# MCU.net
KiCad netlist of a schematic drawn in Altium Designer
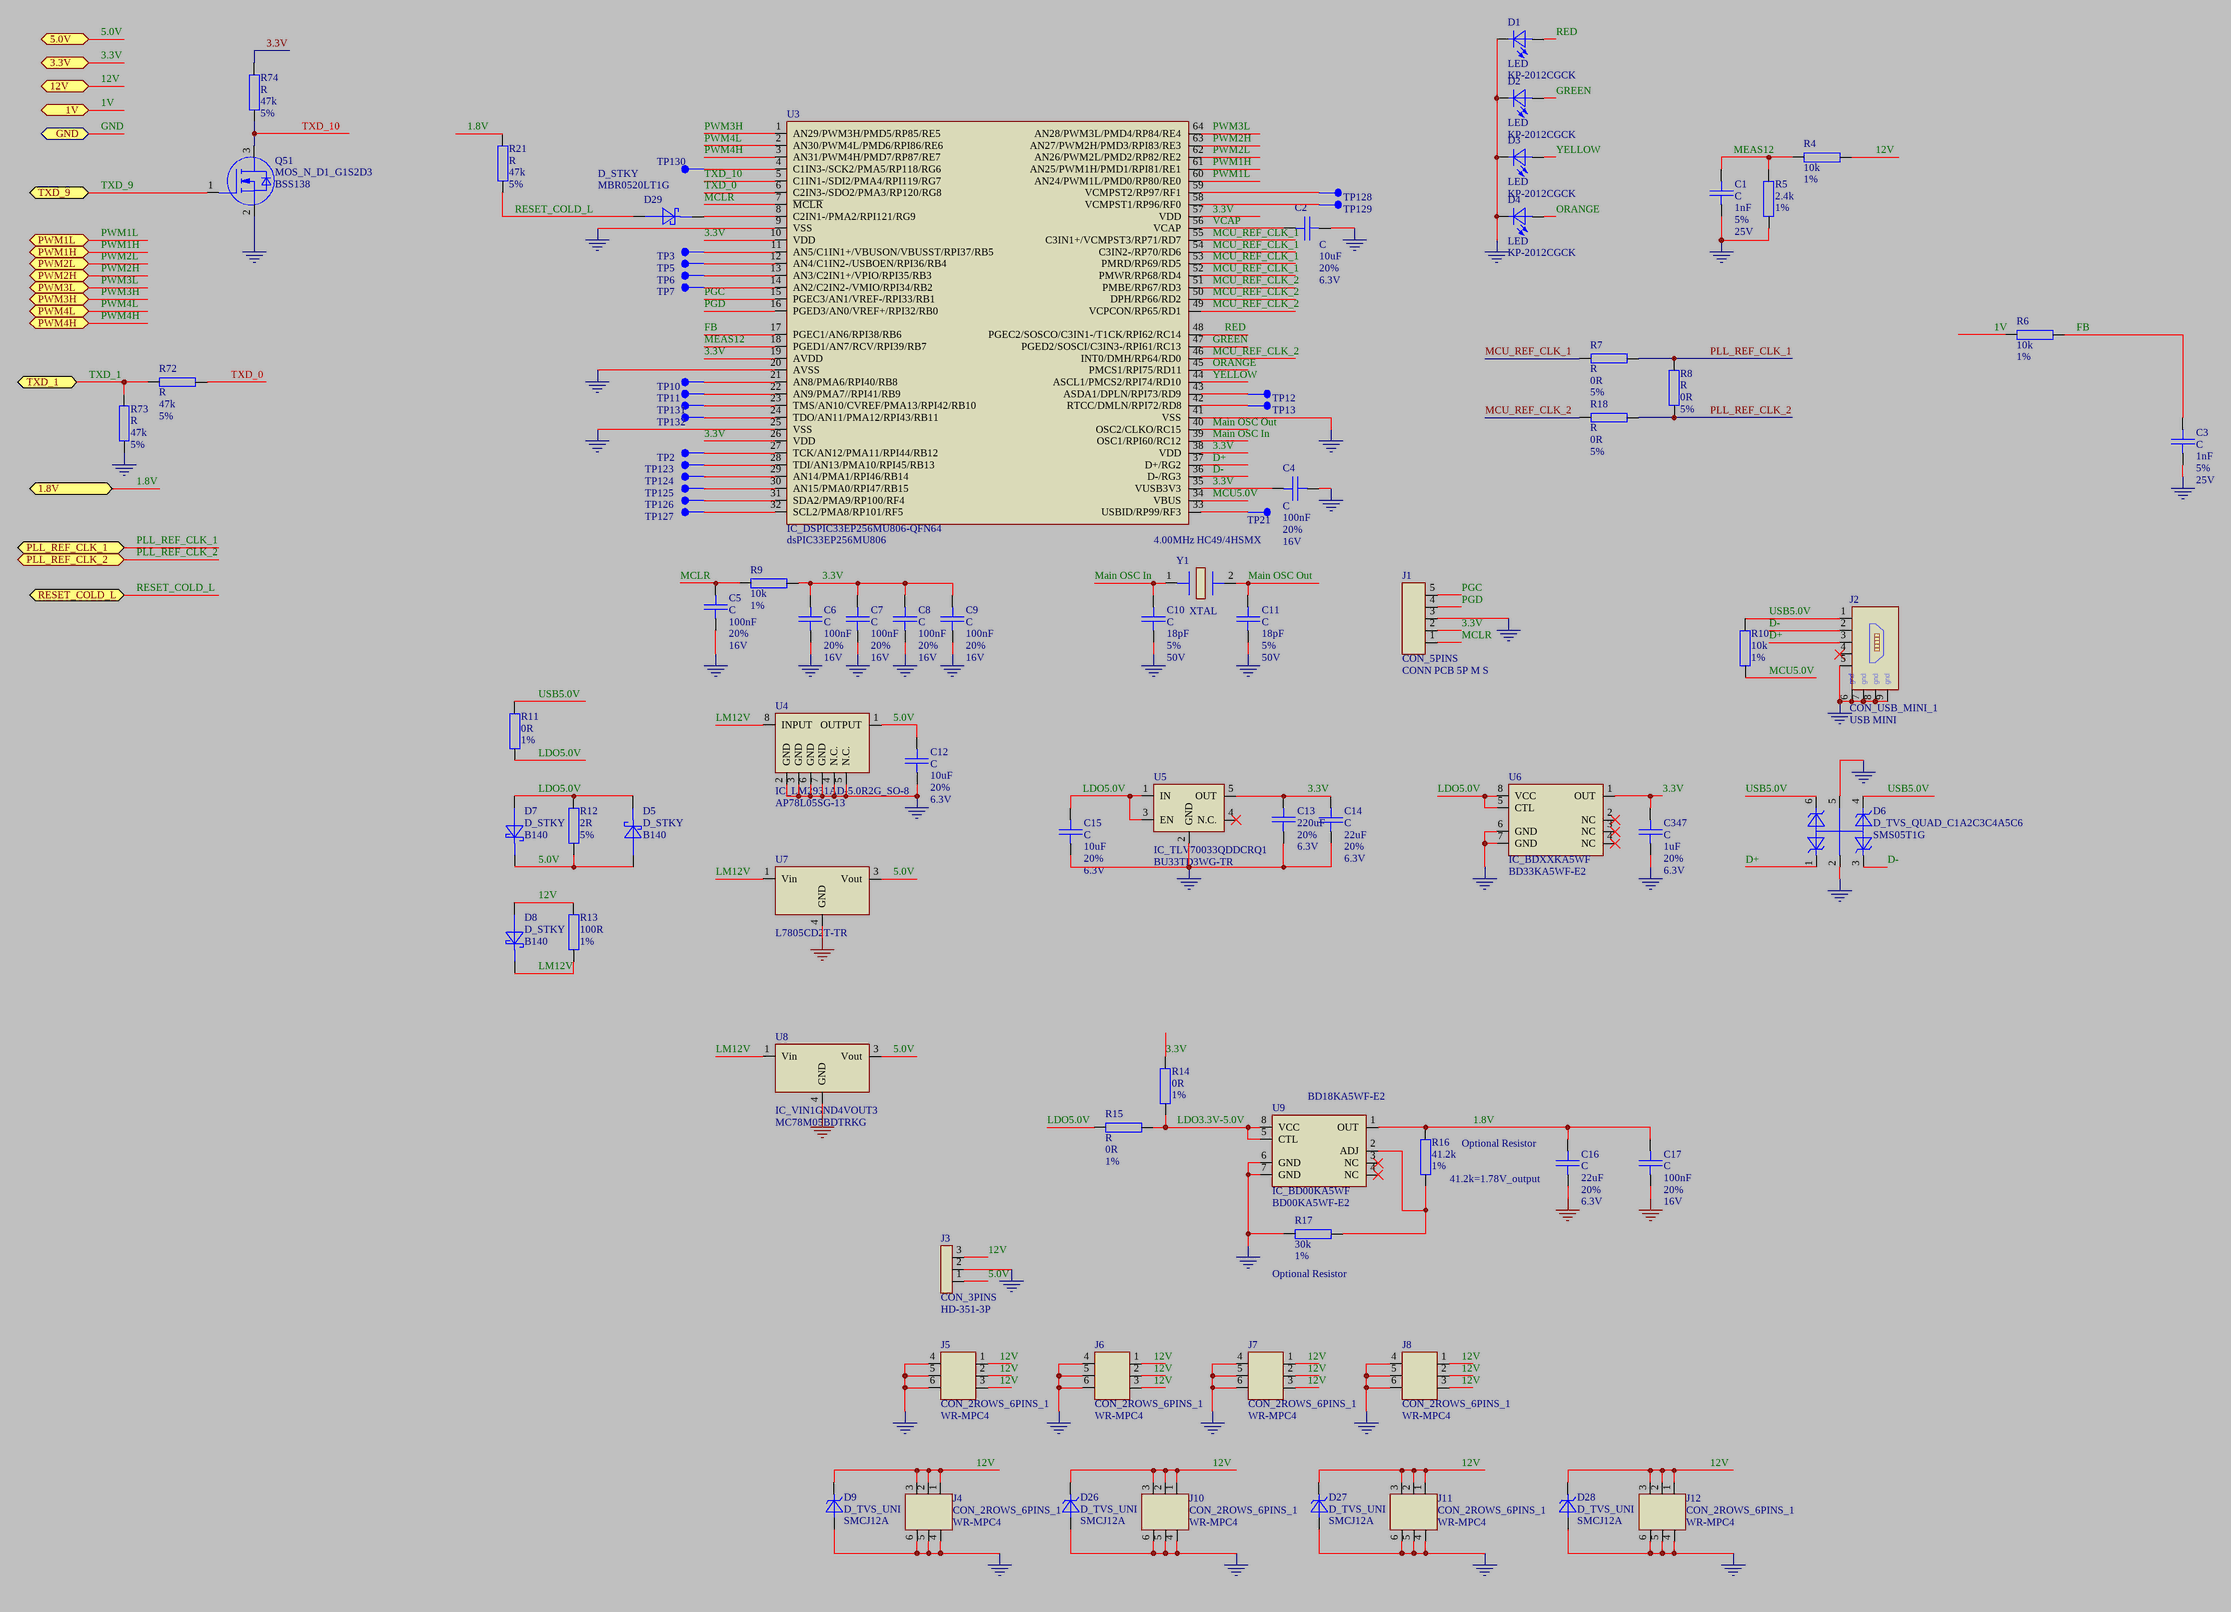
[diagram p0: MCU.SchDoc]

(export (version "E")
  (design (tool "Eeschema 10.0.6"))
  (components
    (comp (ref "C1")
      (value "C")
      (footprint "SMD_0603_CAPC1608X95N")
      (fields
        (field (name "DB_PART_NUMBER") "CAP000024113")
        (field (name "DB_VALUE") "1nF")
        (field (name "DB_TOLERANCE") "5%")
        (field (name "DB_VOLTAGE") "25V")
        (field (name "DB_MANUFACTURER_PART") "KEMET    C0603C102J3RAC")
      )
      (libsource (lib "Database_Libs1") (part "C"))
    )
    (comp (ref "C2")
      (value "C")
      (footprint "SMD_0603_CAPC1608X95N")
      (fields
        (field (name "DB_PART_NUMBER") "CAP000043646")
        (field (name "DB_VALUE") "10uF")
        (field (name "DB_TOLERANCE") "20%")
        (field (name "DB_VOLTAGE") "6.3V")
        (field (name "DB_MANUFACTURER_PART") "KEMET    C0603C106M9PAC")
      )
      (libsource (lib "Database_Libs1") (part "C"))
    )
    (comp (ref "C3")
      (value "C")
      (footprint "SMD_0603_CAPC1608X95N")
      (fields
        (field (name "DB_PART_NUMBER") "CAP000024113")
        (field (name "DB_VALUE") "1nF")
        (field (name "DB_TOLERANCE") "5%")
        (field (name "DB_VOLTAGE") "25V")
        (field (name "DB_MANUFACTURER_PART") "KEMET    C0603C102J3RAC")
      )
      (libsource (lib "Database_Libs1") (part "C"))
    )
    (comp (ref "C4")
      (value "C")
      (footprint "SMD_0402_CAPC1005X55N")
      (fields
        (field (name "DB_PART_NUMBER") "CAP000022751")
        (field (name "DB_VALUE") "100nF")
        (field (name "DB_TOLERANCE") "20%")
        (field (name "DB_VOLTAGE") "16V")
        (field (name "DB_MANUFACTURER_PART") "KEMET    C0402F104M4RAC")
      )
      (libsource (lib "Database_Libs1") (part "C"))
    )
    (comp (ref "C5")
      (value "C")
      (footprint "SMD_0402_CAPC1005X55N")
      (fields
        (field (name "DB_PART_NUMBER") "CAP000022751")
        (field (name "DB_VALUE") "100nF")
        (field (name "DB_TOLERANCE") "20%")
        (field (name "DB_VOLTAGE") "16V")
        (field (name "DB_MANUFACTURER_PART") "KEMET    C0402F104M4RAC")
      )
      (libsource (lib "Database_Libs1") (part "C"))
    )
    (comp (ref "C6")
      (value "C")
      (footprint "SMD_0402_CAPC1005X55N")
      (fields
        (field (name "DB_PART_NUMBER") "CAP000022751")
        (field (name "DB_VALUE") "100nF")
        (field (name "DB_TOLERANCE") "20%")
        (field (name "DB_VOLTAGE") "16V")
        (field (name "DB_MANUFACTURER_PART") "KEMET    C0402F104M4RAC")
      )
      (libsource (lib "Database_Libs1") (part "C"))
    )
    (comp (ref "C7")
      (value "C")
      (footprint "SMD_0402_CAPC1005X55N")
      (fields
        (field (name "DB_PART_NUMBER") "CAP000022751")
        (field (name "DB_VALUE") "100nF")
        (field (name "DB_TOLERANCE") "20%")
        (field (name "DB_VOLTAGE") "16V")
        (field (name "DB_MANUFACTURER_PART") "KEMET    C0402F104M4RAC")
      )
      (libsource (lib "Database_Libs1") (part "C"))
    )
    (comp (ref "C8")
      (value "C")
      (footprint "SMD_0402_CAPC1005X55N")
      (fields
        (field (name "DB_PART_NUMBER") "CAP000022751")
        (field (name "DB_VALUE") "100nF")
        (field (name "DB_TOLERANCE") "20%")
        (field (name "DB_VOLTAGE") "16V")
        (field (name "DB_MANUFACTURER_PART") "KEMET    C0402F104M4RAC")
      )
      (libsource (lib "Database_Libs1") (part "C"))
    )
    (comp (ref "C9")
      (value "C")
      (footprint "SMD_0402_CAPC1005X55N")
      (fields
        (field (name "DB_PART_NUMBER") "CAP000022751")
        (field (name "DB_VALUE") "100nF")
        (field (name "DB_TOLERANCE") "20%")
        (field (name "DB_VOLTAGE") "16V")
        (field (name "DB_MANUFACTURER_PART") "KEMET    C0402F104M4RAC")
      )
      (libsource (lib "Database_Libs1") (part "C"))
    )
    (comp (ref "C10")
      (value "C")
      (footprint "SMD_0603_CAPC1608X95N")
      (fields
        (field (name "DB_PART_NUMBER") "CAP000031922")
        (field (name "DB_VALUE") "18pF")
        (field (name "DB_TOLERANCE") "5%")
        (field (name "DB_VOLTAGE") "50V")
        (field (name "DB_MANUFACTURER_PART") "KEMET    C0603C180J5GAC")
      )
      (libsource (lib "Database_Libs1") (part "C"))
    )
    (comp (ref "C11")
      (value "C")
      (footprint "SMD_0603_CAPC1608X95N")
      (fields
        (field (name "DB_PART_NUMBER") "CAP000031922")
        (field (name "DB_VALUE") "18pF")
        (field (name "DB_TOLERANCE") "5%")
        (field (name "DB_VOLTAGE") "50V")
        (field (name "DB_MANUFACTURER_PART") "KEMET    C0603C180J5GAC")
      )
      (libsource (lib "Database_Libs1") (part "C"))
    )
    (comp (ref "C12")
      (value "C")
      (footprint "SMD_0603_CAPC1608X95N")
      (fields
        (field (name "DB_PART_NUMBER") "CAP000043646")
        (field (name "DB_VALUE") "10uF")
        (field (name "DB_TOLERANCE") "20%")
        (field (name "DB_VOLTAGE") "6.3V")
        (field (name "DB_MANUFACTURER_PART") "KEMET    C0603C106M9PAC")
      )
      (libsource (lib "Database_Libs1") (part "C"))
    )
    (comp (ref "C13")
      (value "C")
      (footprint "SMD_1210_CAPC3225X279N")
      (fields
        (field (name "DB_PART_NUMBER") "CAP000047355")
        (field (name "DB_VALUE") "220uF")
        (field (name "DB_TOLERANCE") "20%")
        (field (name "DB_VOLTAGE") "6.3V")
        (field (name "DB_MANUFACTURER_PART") "SAMSUNG    CL32A227MQVNNNE")
        (field (name "DB_APPROVED_BY") "VSN")
      )
      (libsource (lib "Database_Libs1") (part "C"))
    )
    (comp (ref "C14")
      (value "C")
      (footprint "SMD_0805_CAPC2012X145N")
      (fields
        (field (name "DB_PART_NUMBER") "CAP000043686")
        (field (name "DB_VALUE") "22uF")
        (field (name "DB_TOLERANCE") "20%")
        (field (name "DB_VOLTAGE") "6.3V")
        (field (name "DB_MANUFACTURER_PART") "KEMET    C0805C226M9PAC")
      )
      (libsource (lib "Database_Libs1") (part "C"))
    )
    (comp (ref "C15")
      (value "C")
      (footprint "SMD_0603_CAPC1608X95N")
      (fields
        (field (name "DB_PART_NUMBER") "CAP000043646")
        (field (name "DB_VALUE") "10uF")
        (field (name "DB_TOLERANCE") "20%")
        (field (name "DB_VOLTAGE") "6.3V")
        (field (name "DB_MANUFACTURER_PART") "KEMET    C0603C106M9PAC")
      )
      (libsource (lib "Database_Libs1") (part "C"))
    )
    (comp (ref "C16")
      (value "C")
      (footprint "SMD_0805_CAPC2012X145N")
      (fields
        (field (name "DB_PART_NUMBER") "CAP000043686")
        (field (name "DB_VALUE") "22uF")
        (field (name "DB_TOLERANCE") "20%")
        (field (name "DB_VOLTAGE") "6.3V")
        (field (name "DB_MANUFACTURER_PART") "KEMET    C0805C226M9PAC")
      )
      (libsource (lib "Database_Libs1") (part "C"))
    )
    (comp (ref "C17")
      (value "C")
      (footprint "SMD_0402_CAPC1005X55N")
      (fields
        (field (name "DB_PART_NUMBER") "CAP000022751")
        (field (name "DB_VALUE") "100nF")
        (field (name "DB_TOLERANCE") "20%")
        (field (name "DB_VOLTAGE") "16V")
        (field (name "DB_MANUFACTURER_PART") "KEMET    C0402F104M4RAC")
      )
      (libsource (lib "Database_Libs1") (part "C"))
    )
    (comp (ref "C347")
      (value "C")
      (footprint "SMD_0603_CAPC1608X95N")
      (fields
        (field (name "DB_PART_NUMBER") "CAP000043344")
        (field (name "DB_VALUE") "1uF")
        (field (name "DB_TOLERANCE") "20%")
        (field (name "DB_VOLTAGE") "6.3V")
        (field (name "DB_MANUFACTURER_PART") "KEMET    C0603C105M9PAC")
      )
      (libsource (lib "Database_Libs1") (part "C"))
    )
    (comp (ref "D1")
      (value "LED")
      (footprint "SMD_0805_LED2012X100N")
      (fields
        (field (name "DB_PART_NUMBER") "OPT000000096")
        (field (name "DB_VALUE") "KP-2012CGCK")
        (field (name "DB_MANUFACTURER_PART") "KINGBRIGHT       KP-2012CGCK")
        (field (name "DB_APPROVED_BY") "VSN")
      )
      (libsource (lib "Database_Libs1") (part "LED"))
    )
    (comp (ref "D2")
      (value "LED")
      (footprint "SMD_0805_LED2012X100N")
      (fields
        (field (name "DB_PART_NUMBER") "OPT000000096")
        (field (name "DB_VALUE") "KP-2012CGCK")
        (field (name "DB_MANUFACTURER_PART") "KINGBRIGHT       KP-2012CGCK")
        (field (name "DB_APPROVED_BY") "VSN")
      )
      (libsource (lib "Database_Libs1") (part "LED"))
    )
    (comp (ref "D3")
      (value "LED")
      (footprint "SMD_0805_LED2012X100N")
      (fields
        (field (name "DB_PART_NUMBER") "OPT000000096")
        (field (name "DB_VALUE") "KP-2012CGCK")
        (field (name "DB_MANUFACTURER_PART") "KINGBRIGHT       KP-2012CGCK")
        (field (name "DB_APPROVED_BY") "VSN")
      )
      (libsource (lib "Database_Libs1") (part "LED"))
    )
    (comp (ref "D4")
      (value "LED")
      (footprint "SMD_0805_LED2012X100N")
      (fields
        (field (name "DB_PART_NUMBER") "OPT000000096")
        (field (name "DB_VALUE") "KP-2012CGCK")
        (field (name "DB_MANUFACTURER_PART") "KINGBRIGHT       KP-2012CGCK")
        (field (name "DB_APPROVED_BY") "VSN")
      )
      (libsource (lib "Database_Libs1") (part "LED"))
    )
    (comp (ref "D5")
      (value "D_STKY")
      (footprint "SMD_DO214AC_SMA")
      (fields
        (field (name "DB_PART_NUMBER") "DDE000000580")
        (field (name "DB_VALUE") "B140")
        (field (name "DB_MANUFACTURER_PART") "Diodes        B140")
      )
      (libsource (lib "Database_Libs1") (part "D_STKY"))
    )
    (comp (ref "D6")
      (value "D_TVS_QUAD_C1A2C3C4A5C6")
      (footprint "SMD_SOT457_SOT95P275X110-6N")
      (fields
        (field (name "DB_PART_NUMBER") "DDE000002846")
        (field (name "DB_VALUE") "SMS05T1G")
        (field (name "DB_MANUFACTURER_PART") "ON SEMICONDUCTOR        SMS05T1G")
        (field (name "DB_APPROVED_BY") "VSN")
      )
      (libsource (lib "Database_Libs1") (part "D_TVS_QUAD_C1A2C3C4A5C6"))
    )
    (comp (ref "D7")
      (value "D_STKY")
      (footprint "SMD_DO214AC_SMA")
      (fields
        (field (name "DB_PART_NUMBER") "DDE000000580")
        (field (name "DB_VALUE") "B140")
        (field (name "DB_MANUFACTURER_PART") "Diodes        B140")
      )
      (libsource (lib "Database_Libs1") (part "D_STKY"))
    )
    (comp (ref "D8")
      (value "D_STKY")
      (footprint "SMD_DO214AC_SMA")
      (fields
        (field (name "DB_PART_NUMBER") "DDE000000580")
        (field (name "DB_VALUE") "B140")
        (field (name "DB_MANUFACTURER_PART") "Diodes        B140")
      )
      (libsource (lib "Database_Libs1") (part "D_STKY"))
    )
    (comp (ref "D9")
      (value "D_TVS_UNI")
      (footprint "SMD_DO214AC_SMC")
      (fields
        (field (name "DB_PART_NUMBER") "DDE000001725")
        (field (name "DB_VALUE") "SMCJ12A")
        (field (name "DB_MANUFACTURER_PART") "Diodes        SMCJ12A")
      )
      (libsource (lib "Database_Libs1") (part "D_TVS_UNI"))
    )
    (comp (ref "D26")
      (value "D_TVS_UNI")
      (footprint "SMD_DO214AC_SMC")
      (fields
        (field (name "DB_PART_NUMBER") "DDE000001725")
        (field (name "DB_VALUE") "SMCJ12A")
        (field (name "DB_MANUFACTURER_PART") "Diodes        SMCJ12A")
      )
      (libsource (lib "Database_Libs1") (part "D_TVS_UNI"))
    )
    (comp (ref "D27")
      (value "D_TVS_UNI")
      (footprint "SMD_DO214AC_SMC")
      (fields
        (field (name "DB_PART_NUMBER") "DDE000001725")
        (field (name "DB_VALUE") "SMCJ12A")
        (field (name "DB_MANUFACTURER_PART") "Diodes        SMCJ12A")
      )
      (libsource (lib "Database_Libs1") (part "D_TVS_UNI"))
    )
    (comp (ref "D28")
      (value "D_TVS_UNI")
      (footprint "SMD_DO214AC_SMC")
      (fields
        (field (name "DB_PART_NUMBER") "DDE000001725")
        (field (name "DB_VALUE") "SMCJ12A")
        (field (name "DB_MANUFACTURER_PART") "Diodes        SMCJ12A")
      )
      (libsource (lib "Database_Libs1") (part "D_TVS_UNI"))
    )
    (comp (ref "D29")
      (value "D_STKY")
      (footprint "SMD_R_SOD123_SOD3715X145N")
      (fields
        (field (name "DB_PART_NUMBER") "DDE000000883")
        (field (name "DB_MANUFACTURER_PART") "Diodes        SBR0560S1")
      )
      (libsource (lib "Database_Libs1") (part "D_STKY"))
    )
    (comp (ref "J1")
      (value "CON_5PINS")
      (footprint "PTH_HDRV05W64P254_1X05")
      (fields
        (field (name "DB_PART_NUMBER") "CON000000006")
        (field (name "DB_VALUE") "CONN PCB 5P M S")
        (field (name "DB_MANUFACTURER_PART") "W+P        143-12-005-00")
        (field (name "DB_APPROVED_BY") "VSN")
      )
      (libsource (lib "Database_Libs1") (part "CON_5PINS"))
    )
    (comp (ref "J2")
      (value "CON_USB_MINI_1")
      (footprint "SMD_CON-CVILUX-CU04-SCM15B0")
      (fields
        (field (name "DB_PART_NUMBER") "CON000000048")
        (field (name "DB_VALUE") "USB MINI")
        (field (name "DB_MANUFACTURER_PART") "CVILUX       CU04-SCM15B0-R0-LF")
        (field (name "DB_APPROVED_BY") "VSN")
      )
      (libsource (lib "Database_Libs1") (part "CON_USB_MINI_1"))
    )
    (comp (ref "J3")
      (value "CON_3PINS")
      (footprint "PTH_CON_HD-351-3P")
      (fields
        (field (name "DB_PART_NUMBER") "CON000000272")
        (field (name "DB_VALUE") "HD-351-3P")
        (field (name "DB_MANUFACTURER_PART") "HOW DER      HD-351-3P")
        (field (name "DB_APPROVED_BY") "VSN")
      )
      (libsource (lib "Database_Libs1") (part "CON_3PINS"))
    )
    (comp (ref "J4")
      (value "CON_2ROWS_6PINS_1")
      (footprint "PTH_CON_WR-MRC4-6P_S")
      (fields
        (field (name "DB_PART_NUMBER") "CON000000279")
        (field (name "DB_VALUE") "WR-MPC4")
        (field (name "DB_MANUFACTURER_PART") "WE        	649 006 211 22")
        (field (name "DB_APPROVED_BY") "VSN")
      )
      (libsource (lib "Database_Libs1") (part "CON_2ROWS_6PINS_1"))
    )
    (comp (ref "J5")
      (value "CON_2ROWS_6PINS_1")
      (footprint "PTH_CON_WR-MRC4-6P_S")
      (fields
        (field (name "DB_PART_NUMBER") "CON000000279")
        (field (name "DB_VALUE") "WR-MPC4")
        (field (name "DB_MANUFACTURER_PART") "WE        	649 006 211 22")
        (field (name "DB_APPROVED_BY") "VSN")
      )
      (libsource (lib "Database_Libs1") (part "CON_2ROWS_6PINS_1"))
    )
    (comp (ref "J6")
      (value "CON_2ROWS_6PINS_1")
      (footprint "PTH_CON_WR-MRC4-6P_S")
      (fields
        (field (name "DB_PART_NUMBER") "CON000000279")
        (field (name "DB_VALUE") "WR-MPC4")
        (field (name "DB_MANUFACTURER_PART") "WE        	649 006 211 22")
        (field (name "DB_APPROVED_BY") "VSN")
      )
      (libsource (lib "Database_Libs1") (part "CON_2ROWS_6PINS_1"))
    )
    (comp (ref "J7")
      (value "CON_2ROWS_6PINS_1")
      (footprint "PTH_CON_WR-MRC4-6P_S")
      (fields
        (field (name "DB_PART_NUMBER") "CON000000279")
        (field (name "DB_VALUE") "WR-MPC4")
        (field (name "DB_MANUFACTURER_PART") "WE        	649 006 211 22")
        (field (name "DB_APPROVED_BY") "VSN")
      )
      (libsource (lib "Database_Libs1") (part "CON_2ROWS_6PINS_1"))
    )
    (comp (ref "J8")
      (value "CON_2ROWS_6PINS_1")
      (footprint "PTH_CON_WR-MRC4-6P_S")
      (fields
        (field (name "DB_PART_NUMBER") "CON000000279")
        (field (name "DB_VALUE") "WR-MPC4")
        (field (name "DB_MANUFACTURER_PART") "WE        	649 006 211 22")
        (field (name "DB_APPROVED_BY") "VSN")
      )
      (libsource (lib "Database_Libs1") (part "CON_2ROWS_6PINS_1"))
    )
    (comp (ref "J10")
      (value "CON_2ROWS_6PINS_1")
      (footprint "PTH_CON_WR-MRC4-6P_S")
      (fields
        (field (name "DB_PART_NUMBER") "CON000000279")
        (field (name "DB_VALUE") "WR-MPC4")
        (field (name "DB_MANUFACTURER_PART") "WE        	649 006 211 22")
        (field (name "DB_APPROVED_BY") "VSN")
      )
      (libsource (lib "Database_Libs1") (part "CON_2ROWS_6PINS_1"))
    )
    (comp (ref "J11")
      (value "CON_2ROWS_6PINS_1")
      (footprint "PTH_CON_WR-MRC4-6P_S")
      (fields
        (field (name "DB_PART_NUMBER") "CON000000279")
        (field (name "DB_VALUE") "WR-MPC4")
        (field (name "DB_MANUFACTURER_PART") "WE        	649 006 211 22")
        (field (name "DB_APPROVED_BY") "VSN")
      )
      (libsource (lib "Database_Libs1") (part "CON_2ROWS_6PINS_1"))
    )
    (comp (ref "J12")
      (value "CON_2ROWS_6PINS_1")
      (footprint "PTH_CON_WR-MRC4-6P_S")
      (fields
        (field (name "DB_PART_NUMBER") "CON000000279")
        (field (name "DB_VALUE") "WR-MPC4")
        (field (name "DB_MANUFACTURER_PART") "WE        	649 006 211 22")
        (field (name "DB_APPROVED_BY") "VSN")
      )
      (libsource (lib "Database_Libs1") (part "CON_2ROWS_6PINS_1"))
    )
    (comp (ref "Q51")
      (value "MOS_N_D1_G1S2D3")
      (footprint "SMD_SOT23_SOT95P240X112-3N")
      (fields
        (field (name "DB_PART_NUMBER") "TRA000001460")
        (field (name "DB_VALUE") "BSS138")
        (field (name "DB_MANUFACTURER_PART") "FAIRCHILD        BSS138LT1G")
        (field (name "DB_APPROVED_BY") "VSN")
      )
      (libsource (lib "Database_Libs1") (part "MOS_N_D1_G1S2D3"))
    )
    (comp (ref "R4")
      (value "R")
      (footprint "SMD_0603_RESC1608X55N")
      (fields
        (field (name "DB_PART_NUMBER") "RES000008663")
        (field (name "DB_VALUE") "10k")
        (field (name "DB_TOLERANCE") "1%")
        (field (name "DB_MANUFACTURER_PART") "YAGEO    RC0603FR-0710KL")
        (field (name "DB_APPROVED_BY") "VSN")
      )
      (libsource (lib "Database_Libs1") (part "R"))
    )
    (comp (ref "R5")
      (value "R")
      (footprint "SMD_0603_RESC1608X55N")
      (fields
        (field (name "DB_PART_NUMBER") "RES000006261")
        (field (name "DB_VALUE") "2.4k")
        (field (name "DB_TOLERANCE") "1%")
        (field (name "DB_MANUFACTURER_PART") "YAGEO    RC0603FR-072K4")
      )
      (libsource (lib "Database_Libs1") (part "R"))
    )
    (comp (ref "R6")
      (value "R")
      (footprint "SMD_0603_RESC1608X55N")
      (fields
        (field (name "DB_PART_NUMBER") "RES000008663")
        (field (name "DB_VALUE") "10k")
        (field (name "DB_TOLERANCE") "1%")
        (field (name "DB_MANUFACTURER_PART") "YAGEO    RC0603FR-0710KL")
        (field (name "DB_APPROVED_BY") "VSN")
      )
      (libsource (lib "Database_Libs1") (part "R"))
    )
    (comp (ref "R7")
      (value "R")
      (footprint "SMD_0603_RESC1608X55N")
      (fields
        (field (name "DB_PART_NUMBER") "RES000006349")
        (field (name "DB_VALUE") "0R")
        (field (name "DB_TOLERANCE") "5%")
        (field (name "DB_MANUFACTURER_PART") "YAGEO    RC0603JR-070R")
      )
      (libsource (lib "Database_Libs1") (part "R"))
    )
    (comp (ref "R8")
      (value "R")
      (footprint "SMD_0603_RESC1608X55N")
      (fields
        (field (name "DB_PART_NUMBER") "RES000006349")
        (field (name "DB_VALUE") "0R")
        (field (name "DB_TOLERANCE") "5%")
        (field (name "DB_MANUFACTURER_PART") "YAGEO    RC0603JR-070R")
      )
      (libsource (lib "Database_Libs1") (part "R"))
    )
    (comp (ref "R9")
      (value "R")
      (footprint "SMD_0603_RESC1608X55N")
      (fields
        (field (name "DB_PART_NUMBER") "RES000008663")
        (field (name "DB_VALUE") "10k")
        (field (name "DB_TOLERANCE") "1%")
        (field (name "DB_MANUFACTURER_PART") "YAGEO    RC0603FR-0710KL")
        (field (name "DB_APPROVED_BY") "VSN")
      )
      (libsource (lib "Database_Libs1") (part "R"))
    )
    (comp (ref "R10")
      (value "R")
      (footprint "SMD_0603_RESC1608X55N")
      (fields
        (field (name "DB_PART_NUMBER") "RES000008663")
        (field (name "DB_VALUE") "10k")
        (field (name "DB_TOLERANCE") "1%")
        (field (name "DB_MANUFACTURER_PART") "YAGEO    RC0603FR-0710KL")
        (field (name "DB_APPROVED_BY") "VSN")
      )
      (libsource (lib "Database_Libs1") (part "R"))
    )
    (comp (ref "R11")
      (value "R")
      (footprint "SMD_0603_RESC1608X55N")
      (fields
        (field (name "DB_PART_NUMBER") "RES000008926")
        (field (name "DB_VALUE") "0R")
        (field (name "DB_TOLERANCE") "1%")
        (field (name "DB_MANUFACTURER_PART") "YAGEO    AC0603FR-070RL")
        (field (name "DB_APPROVED_BY") "VSN")
      )
      (libsource (lib "Database_Libs1") (part "R"))
    )
    (comp (ref "R12")
      (value "R")
      (footprint "SMD_1206_RESC3216X65N")
      (fields
        (field (name "DB_PART_NUMBER") "RES000007051")
        (field (name "DB_VALUE") "2R")
        (field (name "DB_TOLERANCE") "5%")
        (field (name "DB_MANUFACTURER_PART") "YAGEO    RC1206JR-072R")
      )
      (libsource (lib "Database_Libs1") (part "R"))
    )
    (comp (ref "R13")
      (value "R")
      (footprint "SMD_1206_RESC3216X65N")
      (fields
        (field (name "DB_PART_NUMBER") "RES000006922")
        (field (name "DB_VALUE") "100R")
        (field (name "DB_TOLERANCE") "1%")
        (field (name "DB_MANUFACTURER_PART") "YAGEO    RC1206FR-07100R")
      )
      (libsource (lib "Database_Libs1") (part "R"))
    )
    (comp (ref "R14")
      (value "R")
      (footprint "SMD_1206_RESC3216X65N")
      (fields
        (field (name "DB_PART_NUMBER") "RES000008756")
        (field (name "DB_VALUE") "0R")
        (field (name "DB_TOLERANCE") "1%")
        (field (name "DB_MANUFACTURER_PART") "YAGEO    AC1206FR-070RL")
        (field (name "DB_APPROVED_BY") "VSN")
      )
      (libsource (lib "Database_Libs1") (part "R"))
    )
    (comp (ref "R15")
      (value "R")
      (footprint "SMD_1206_RESC3216X65N")
      (fields
        (field (name "DB_PART_NUMBER") "RES000008756")
        (field (name "DB_VALUE") "0R")
        (field (name "DB_TOLERANCE") "1%")
        (field (name "DB_MANUFACTURER_PART") "YAGEO    AC1206FR-070RL")
        (field (name "DB_APPROVED_BY") "VSN")
      )
      (libsource (lib "Database_Libs1") (part "R"))
    )
    (comp (ref "R16")
      (value "R")
      (footprint "SMD_0603_RESC1608X55N")
      (fields
        (field (name "DB_PART_NUMBER") "RES000001590")
        (field (name "DB_VALUE") "41.2k")
        (field (name "DB_TOLERANCE") "1%")
        (field (name "DB_MANUFACTURER_PART") "YAGEO    RC0603FR-0741K2")
      )
      (libsource (lib "Database_Libs1") (part "R"))
    )
    (comp (ref "R17")
      (value "R")
      (footprint "SMD_0603_RESC1608X55N")
      (fields
        (field (name "DB_PART_NUMBER") "RES000006287")
        (field (name "DB_VALUE") "30k")
        (field (name "DB_TOLERANCE") "1%")
        (field (name "DB_MANUFACTURER_PART") "YAGEO    RC0603FR-0730K")
      )
      (libsource (lib "Database_Libs1") (part "R"))
    )
    (comp (ref "R18")
      (value "R")
      (footprint "SMD_0603_RESC1608X55N")
      (fields
        (field (name "DB_PART_NUMBER") "RES000006349")
        (field (name "DB_VALUE") "0R")
        (field (name "DB_TOLERANCE") "5%")
        (field (name "DB_MANUFACTURER_PART") "YAGEO    RC0603JR-070R")
      )
      (libsource (lib "Database_Libs1") (part "R"))
    )
    (comp (ref "R21")
      (value "R")
      (footprint "SMD_0603_RESC1608X55N")
      (fields
        (field (name "DB_PART_NUMBER") "RES000006462")
        (field (name "DB_VALUE") "47k")
        (field (name "DB_TOLERANCE") "5%")
        (field (name "DB_MANUFACTURER_PART") "YAGEO    RC0603JR-0747K")
      )
      (libsource (lib "Database_Libs1") (part "R"))
    )
    (comp (ref "R72")
      (value "R")
      (footprint "SMD_0603_RESC1608X55N")
      (fields
        (field (name "DB_PART_NUMBER") "RES000006462")
        (field (name "DB_VALUE") "47k")
        (field (name "DB_TOLERANCE") "5%")
        (field (name "DB_MANUFACTURER_PART") "YAGEO    RC0603JR-0747K")
      )
      (libsource (lib "Database_Libs1") (part "R"))
    )
    (comp (ref "R73")
      (value "R")
      (footprint "SMD_0603_RESC1608X55N")
      (fields
        (field (name "DB_PART_NUMBER") "RES000006462")
        (field (name "DB_VALUE") "47k")
        (field (name "DB_TOLERANCE") "5%")
        (field (name "DB_MANUFACTURER_PART") "YAGEO    RC0603JR-0747K")
      )
      (libsource (lib "Database_Libs1") (part "R"))
    )
    (comp (ref "R74")
      (value "R")
      (footprint "SMD_0603_RESC1608X55N")
      (fields
        (field (name "DB_PART_NUMBER") "RES000006462")
        (field (name "DB_VALUE") "47k")
        (field (name "DB_TOLERANCE") "5%")
        (field (name "DB_MANUFACTURER_PART") "YAGEO    RC0603JR-0747K")
      )
      (libsource (lib "Database_Libs1") (part "R"))
    )
    (comp (ref "TP2")
      (value "TEST_POINT_1")
      (footprint "SMD_TP_100-254")
      (fields (field (name "DB_PART_NUMBER") "TPO000000001"))
      (libsource (lib "Database_Libs1") (part "TEST_POINT_1"))
    )
    (comp (ref "TP3")
      (value "TEST_POINT_1")
      (footprint "SMD_TP_100-254")
      (fields (field (name "DB_PART_NUMBER") "TPO000000001"))
      (libsource (lib "Database_Libs1") (part "TEST_POINT_1"))
    )
    (comp (ref "TP5")
      (value "TEST_POINT_1")
      (footprint "SMD_TP_100-254")
      (fields (field (name "DB_PART_NUMBER") "TPO000000001"))
      (libsource (lib "Database_Libs1") (part "TEST_POINT_1"))
    )
    (comp (ref "TP6")
      (value "TEST_POINT_1")
      (footprint "SMD_TP_100-254")
      (fields (field (name "DB_PART_NUMBER") "TPO000000001"))
      (libsource (lib "Database_Libs1") (part "TEST_POINT_1"))
    )
    (comp (ref "TP7")
      (value "TEST_POINT_1")
      (footprint "SMD_TP_100-254")
      (fields (field (name "DB_PART_NUMBER") "TPO000000001"))
      (libsource (lib "Database_Libs1") (part "TEST_POINT_1"))
    )
    (comp (ref "TP10")
      (value "TEST_POINT_1")
      (footprint "SMD_TP_100-254")
      (fields (field (name "DB_PART_NUMBER") "TPO000000001"))
      (libsource (lib "Database_Libs1") (part "TEST_POINT_1"))
    )
    (comp (ref "TP11")
      (value "TEST_POINT_1")
      (footprint "SMD_TP_100-254")
      (fields (field (name "DB_PART_NUMBER") "TPO000000001"))
      (libsource (lib "Database_Libs1") (part "TEST_POINT_1"))
    )
    (comp (ref "TP12")
      (value "TEST_POINT_1")
      (footprint "SMD_TP_100-254")
      (fields (field (name "DB_PART_NUMBER") "TPO000000001"))
      (libsource (lib "Database_Libs1") (part "TEST_POINT_1"))
    )
    (comp (ref "TP13")
      (value "TEST_POINT_1")
      (footprint "SMD_TP_100-254")
      (fields (field (name "DB_PART_NUMBER") "TPO000000001"))
      (libsource (lib "Database_Libs1") (part "TEST_POINT_1"))
    )
    (comp (ref "TP21")
      (value "TEST_POINT_1")
      (footprint "SMD_TP_100-254")
      (fields (field (name "DB_PART_NUMBER") "TPO000000001"))
      (libsource (lib "Database_Libs1") (part "TEST_POINT_1"))
    )
    (comp (ref "TP123")
      (value "TEST_POINT_1")
      (footprint "SMD_TP_100-254")
      (fields (field (name "DB_PART_NUMBER") "TPO000000001"))
      (libsource (lib "Database_Libs1") (part "TEST_POINT_1"))
    )
    (comp (ref "TP124")
      (value "TEST_POINT_1")
      (footprint "SMD_TP_100-254")
      (fields (field (name "DB_PART_NUMBER") "TPO000000001"))
      (libsource (lib "Database_Libs1") (part "TEST_POINT_1"))
    )
    (comp (ref "TP125")
      (value "TEST_POINT_1")
      (footprint "SMD_TP_100-254")
      (fields (field (name "DB_PART_NUMBER") "TPO000000001"))
      (libsource (lib "Database_Libs1") (part "TEST_POINT_1"))
    )
    (comp (ref "TP126")
      (value "TEST_POINT_1")
      (footprint "SMD_TP_100-254")
      (fields (field (name "DB_PART_NUMBER") "TPO000000001"))
      (libsource (lib "Database_Libs1") (part "TEST_POINT_1"))
    )
    (comp (ref "TP127")
      (value "TEST_POINT_1")
      (footprint "SMD_TP_100-254")
      (fields (field (name "DB_PART_NUMBER") "TPO000000001"))
      (libsource (lib "Database_Libs1") (part "TEST_POINT_1"))
    )
    (comp (ref "TP128")
      (value "TEST_POINT_1")
      (footprint "SMD_TP_100-254")
      (fields (field (name "DB_PART_NUMBER") "TPO000000001"))
      (libsource (lib "Database_Libs1") (part "TEST_POINT_1"))
    )
    (comp (ref "TP129")
      (value "TEST_POINT_1")
      (footprint "SMD_TP_100-254")
      (fields (field (name "DB_PART_NUMBER") "TPO000000001"))
      (libsource (lib "Database_Libs1") (part "TEST_POINT_1"))
    )
    (comp (ref "TP130")
      (value "TEST_POINT_1")
      (footprint "SMD_TP_100-254")
      (fields (field (name "DB_PART_NUMBER") "TPO000000001"))
      (libsource (lib "Database_Libs1") (part "TEST_POINT_1"))
    )
    (comp (ref "TP131")
      (value "TEST_POINT_1")
      (footprint "SMD_TP_100-254")
      (fields (field (name "DB_PART_NUMBER") "TPO000000001"))
      (libsource (lib "Database_Libs1") (part "TEST_POINT_1"))
    )
    (comp (ref "TP132")
      (value "TEST_POINT_1")
      (footprint "SMD_TP_100-254")
      (fields (field (name "DB_PART_NUMBER") "TPO000000001"))
      (libsource (lib "Database_Libs1") (part "TEST_POINT_1"))
    )
    (comp (ref "U3")
      (value "IC_DSPIC33EP256MU806-QFN64")
      (footprint "SMD_QFP50P1200X1200X120-64N")
      (fields
        (field (name "DB_PART_NUMBER") "MCU000000070")
        (field (name "DB_VALUE") "dsPIC33EP256MU806")
        (field (name "DB_MANUFACTURER_PART") "MICROCHIP        DSPIC33EP256MU806-E/PT")
        (field (name "DB_APPROVED_BY") "VSN")
      )
      (libsource (lib "Database_Libs1") (part "IC_DSPIC33EP256MU806-QFN64"))
    )
    (comp (ref "U4")
      (value "IC_LM2931AD-5.0R2G_SO-8")
      (footprint "SMD_SOIC127P600X175-8N")
      (fields
        (field (name "DB_PART_NUMBER") "PSU000000125")
        (field (name "DB_VALUE") "AP78L05SG-13")
        (field (name "DB_MANUFACTURER_PART") "DIODES        AP78L05SG-13")
        (field (name "DB_APPROVED_BY") "VSN")
      )
      (libsource (lib "Database_Libs1") (part "IC_LM2931AD-5.0R2G_SO-8"))
    )
    (comp (ref "U5")
      (value "IC_TLV70033QDDCRQ1")
      (footprint "SMD_SOT95P280X135-5N")
      (fields
        (field (name "DB_PART_NUMBER") "PSU000000126")
        (field (name "DB_VALUE") "BU33TD3WG-TR")
        (field (name "DB_MANUFACTURER_PART") "ROHM     BU33TD3WG-TR")
        (field (name "DB_APPROVED_BY") "VSN")
      )
      (libsource (lib "Database_Libs1") (part "IC_TLV70033QDDCRQ1"))
    )
    (comp (ref "U6")
      (value "IC_BDXXKA5WF")
      (footprint "SMD_SOIC127P620X160-8N")
      (fields
        (field (name "DB_PART_NUMBER") "PSU000000127")
        (field (name "DB_VALUE") "BD33KA5WF-E2")
        (field (name "DB_MANUFACTURER_PART") "ROHM        BD33KA5WF-E2")
        (field (name "DB_APPROVED_BY") "VSN")
      )
      (libsource (lib "Database_Libs1") (part "IC_BDXXKA5WF"))
    )
    (comp (ref "U7")
      (value "IC_IN1OUT3GND4")
      (footprint "SMD_TO254P1542X460-3_4N")
      (fields
        (field (name "DB_PART_NUMBER") "PSU000000129")
        (field (name "DB_VALUE") "L7805CD2T-TR")
        (field (name "DB_MANUFACTURER_PART") "ST       L7805CD2T-TR")
        (field (name "DB_APPROVED_BY") "VSN")
      )
      (libsource (lib "Database_Libs1") (part "IC_IN1OUT3GND4"))
    )
    (comp (ref "U8")
      (value "IC_VIN1GND4VOUT3")
      (footprint "SMD_TO229P991X239-4N_DPAK")
      (fields
        (field (name "DB_PART_NUMBER") "PSU000000031")
        (field (name "DB_VALUE") "MC78M05BDTRKG")
        (field (name "DB_MANUFACTURER_PART") "ON Semiconductor       MC78M05BDTRKG")
        (field (name "DB_APPROVED_BY") "VSN")
      )
      (libsource (lib "Database_Libs1") (part "IC_VIN1GND4VOUT3"))
    )
    (comp (ref "U9")
      (value "IC_BD00KA5WF")
      (footprint "SMD_SOIC127P620X160-8N")
      (fields
        (field (name "DB_PART_NUMBER") "PSU000000128")
        (field (name "DB_VALUE") "BD00KA5WF-E2")
        (field (name "DB_MANUFACTURER_PART") "ROHM        BD00KA5WF-E2")
        (field (name "DB_APPROVED_BY") "VSN")
      )
      (libsource (lib "Database_Libs1") (part "IC_BD00KA5WF"))
    )
    (comp (ref "Y1")
      (value "XTAL")
      (footprint "SMD_HC49_XTAL1140X480X420N")
      (fields
        (field (name "DB_PART_NUMBER") "OSC000000012")
        (field (name "DB_VALUE") "4.00MHz HC49/4HSMX")
        (field (name "DB_MANUFACTURER_PART") "IQD       4.00MHz HC49/4HSMX")
        (field (name "DB_APPROVED_BY") "VSN")
      )
      (libsource (lib "Database_Libs1") (part "XTAL"))
    )
  )
  (nets
    (net (code "1") (name "/1.8V") (class "Default")
      (node (ref "C16") (pin "1") (pinfunction "1_1") (pintype "passive"))
      (node (ref "C17") (pin "1") (pinfunction "1_1") (pintype "passive"))
      (node (ref "R16") (pin "1") (pinfunction "1_1") (pintype "passive"))
      (node (ref "R21") (pin "1") (pinfunction "1_1") (pintype "passive"))
      (node (ref "U9") (pin "1") (pinfunction "OUT_1") (pintype "passive"))
    )
    (net (code "2") (name "/1V") (class "Default")
      (node (ref "R6") (pin "2") (pinfunction "2_2") (pintype "passive"))
    )
    (net (code "3") (name "/3.3V") (class "Default")
      (node (ref "C13") (pin "2") (pinfunction "2_2") (pintype "passive"))
      (node (ref "C14") (pin "1") (pinfunction "1_1") (pintype "passive"))
      (node (ref "C347") (pin "1") (pinfunction "1_1") (pintype "passive"))
      (node (ref "C4") (pin "1") (pinfunction "1_1") (pintype "passive"))
      (node (ref "C6") (pin "1") (pinfunction "1_1") (pintype "passive"))
      (node (ref "C7") (pin "1") (pinfunction "1_1") (pintype "passive"))
      (node (ref "C8") (pin "1") (pinfunction "1_1") (pintype "passive"))
      (node (ref "C9") (pin "1") (pinfunction "1_1") (pintype "passive"))
      (node (ref "J1") (pin "2") (pinfunction "2_2") (pintype "passive"))
      (node (ref "R14") (pin "2") (pinfunction "2_2") (pintype "passive"))
      (node (ref "R74") (pin "1") (pinfunction "1_1") (pintype "passive"))
      (node (ref "R9") (pin "2") (pinfunction "2_2") (pintype "passive"))
      (node (ref "U3") (pin "10") (pinfunction "VDD_10") (pintype "passive"))
      (node (ref "U3") (pin "19") (pinfunction "AVDD_19") (pintype "passive"))
      (node (ref "U3") (pin "26") (pinfunction "VDD_26") (pintype "passive"))
      (node (ref "U3") (pin "35") (pinfunction "VUSB3V3_35") (pintype "passive"))
      (node (ref "U3") (pin "38") (pinfunction "VDD_38") (pintype "passive"))
      (node (ref "U3") (pin "57") (pinfunction "VDD_57") (pintype "passive"))
      (node (ref "U5") (pin "5") (pinfunction "OUT_5") (pintype "passive"))
      (node (ref "U6") (pin "1") (pinfunction "OUT_1") (pintype "passive"))
    )
    (net (code "4") (name "/5.0V") (class "Default")
      (node (ref "C12") (pin "1") (pinfunction "1_1") (pintype "passive"))
      (node (ref "D5") (pin "2") (pinfunction "A_2") (pintype "passive"))
      (node (ref "D7") (pin "1") (pinfunction "C_1") (pintype "passive"))
      (node (ref "J3") (pin "1") (pinfunction "1_1") (pintype "passive"))
      (node (ref "R12") (pin "1") (pinfunction "1_1") (pintype "passive"))
      (node (ref "U4") (pin "1") (pinfunction "OUTPUT_1") (pintype "passive"))
      (node (ref "U7") (pin "3") (pinfunction "Vout_3") (pintype "passive"))
      (node (ref "U8") (pin "3") (pinfunction "Vout_3") (pintype "passive"))
    )
    (net (code "5") (name "/12V") (class "Default")
      (node (ref "D26") (pin "1") (pinfunction "C_1") (pintype "passive"))
      (node (ref "D27") (pin "1") (pinfunction "C_1") (pintype "passive"))
      (node (ref "D28") (pin "1") (pinfunction "C_1") (pintype "passive"))
      (node (ref "D8") (pin "2") (pinfunction "A_2") (pintype "passive"))
      (node (ref "D9") (pin "1") (pinfunction "C_1") (pintype "passive"))
      (node (ref "J10") (pin "1") (pinfunction "1_1") (pintype "passive"))
      (node (ref "J10") (pin "2") (pinfunction "2_2") (pintype "passive"))
      (node (ref "J10") (pin "3") (pinfunction "3_3") (pintype "passive"))
      (node (ref "J11") (pin "1") (pinfunction "1_1") (pintype "passive"))
      (node (ref "J11") (pin "2") (pinfunction "2_2") (pintype "passive"))
      (node (ref "J11") (pin "3") (pinfunction "3_3") (pintype "passive"))
      (node (ref "J12") (pin "1") (pinfunction "1_1") (pintype "passive"))
      (node (ref "J12") (pin "2") (pinfunction "2_2") (pintype "passive"))
      (node (ref "J12") (pin "3") (pinfunction "3_3") (pintype "passive"))
      (node (ref "J3") (pin "3") (pinfunction "3_3") (pintype "passive"))
      (node (ref "J4") (pin "1") (pinfunction "1_1") (pintype "passive"))
      (node (ref "J4") (pin "2") (pinfunction "2_2") (pintype "passive"))
      (node (ref "J4") (pin "3") (pinfunction "3_3") (pintype "passive"))
      (node (ref "J5") (pin "1") (pinfunction "1_1") (pintype "passive"))
      (node (ref "J5") (pin "2") (pinfunction "2_2") (pintype "passive"))
      (node (ref "J5") (pin "3") (pinfunction "3_3") (pintype "passive"))
      (node (ref "J6") (pin "1") (pinfunction "1_1") (pintype "passive"))
      (node (ref "J6") (pin "2") (pinfunction "2_2") (pintype "passive"))
      (node (ref "J6") (pin "3") (pinfunction "3_3") (pintype "passive"))
      (node (ref "J7") (pin "1") (pinfunction "1_1") (pintype "passive"))
      (node (ref "J7") (pin "2") (pinfunction "2_2") (pintype "passive"))
      (node (ref "J7") (pin "3") (pinfunction "3_3") (pintype "passive"))
      (node (ref "J8") (pin "1") (pinfunction "1_1") (pintype "passive"))
      (node (ref "J8") (pin "2") (pinfunction "2_2") (pintype "passive"))
      (node (ref "J8") (pin "3") (pinfunction "3_3") (pintype "passive"))
      (node (ref "R13") (pin "2") (pinfunction "2_2") (pintype "passive"))
      (node (ref "R4") (pin "1") (pinfunction "1_1") (pintype "passive"))
    )
    (net (code "6") (name "/D+") (class "Default")
      (node (ref "D6") (pin "1") (pinfunction "1_1") (pintype "passive"))
      (node (ref "J2") (pin "3") (pinfunction "3_3") (pintype "passive"))
      (node (ref "U3") (pin "37") (pinfunction "D+/RG2_37") (pintype "passive"))
    )
    (net (code "7") (name "/D-") (class "Default")
      (node (ref "D6") (pin "3") (pinfunction "3_3") (pintype "passive"))
      (node (ref "J2") (pin "2") (pinfunction "2_2") (pintype "passive"))
      (node (ref "U3") (pin "36") (pinfunction "D-/RG3_36") (pintype "passive"))
    )
    (net (code "8") (name "/FB") (class "Default")
      (node (ref "C3") (pin "1") (pinfunction "1_1") (pintype "passive"))
      (node (ref "R6") (pin "1") (pinfunction "1_1") (pintype "passive"))
      (node (ref "U3") (pin "17") (pinfunction "PGEC1/AN6/RPI38/RB6_17") (pintype "passive"))
    )
    (net (code "9") (name "/GREEN") (class "Default")
      (node (ref "D2") (pin "2") (pinfunction "A_2") (pintype "passive"))
      (node (ref "U3") (pin "47") (pinfunction "PGED2/SOSCI/C3IN3-/RPI61/RC13_47") (pintype "passive"))
    )
    (net (code "10") (name "/LDO3.3V-5.0V") (class "Default")
      (node (ref "R14") (pin "1") (pinfunction "1_1") (pintype "passive"))
      (node (ref "R15") (pin "1") (pinfunction "1_1") (pintype "passive"))
      (node (ref "U9") (pin "5") (pinfunction "CTL_5") (pintype "passive"))
      (node (ref "U9") (pin "8") (pinfunction "VCC_8") (pintype "passive"))
    )
    (net (code "11") (name "/LDO5.0V") (class "Default")
      (node (ref "C15") (pin "1") (pinfunction "1_1") (pintype "passive"))
      (node (ref "D5") (pin "1") (pinfunction "C_1") (pintype "passive"))
      (node (ref "D7") (pin "2") (pinfunction "A_2") (pintype "passive"))
      (node (ref "R11") (pin "1") (pinfunction "1_1") (pintype "passive"))
      (node (ref "R12") (pin "2") (pinfunction "2_2") (pintype "passive"))
      (node (ref "R15") (pin "2") (pinfunction "2_2") (pintype "passive"))
      (node (ref "U5") (pin "1") (pinfunction "IN_1") (pintype "passive"))
      (node (ref "U5") (pin "3") (pinfunction "EN_3") (pintype "passive"))
      (node (ref "U6") (pin "5") (pinfunction "CTL_5") (pintype "passive"))
      (node (ref "U6") (pin "8") (pinfunction "VCC_8") (pintype "passive"))
    )
    (net (code "12") (name "/LM12V") (class "Default")
      (node (ref "D8") (pin "1") (pinfunction "C_1") (pintype "passive"))
      (node (ref "R13") (pin "1") (pinfunction "1_1") (pintype "passive"))
      (node (ref "U4") (pin "8") (pinfunction "INPUT_8") (pintype "passive"))
      (node (ref "U7") (pin "1") (pinfunction "Vin_1") (pintype "passive"))
      (node (ref "U8") (pin "1") (pinfunction "Vin_1") (pintype "passive"))
    )
    (net (code "13") (name "/MCLR") (class "Default")
      (node (ref "C5") (pin "1") (pinfunction "1_1") (pintype "passive"))
      (node (ref "J1") (pin "1") (pinfunction "1_1") (pintype "passive"))
      (node (ref "R9") (pin "1") (pinfunction "1_1") (pintype "passive"))
      (node (ref "U3") (pin "7") (pinfunction "~{MCLR}_7") (pintype "passive"))
    )
    (net (code "14") (name "/MCU5.0V") (class "Default")
      (node (ref "R10") (pin "2") (pinfunction "2_2") (pintype "passive"))
      (node (ref "U3") (pin "34") (pinfunction "VBUS_34") (pintype "passive"))
    )
    (net (code "15") (name "/MCU_REF_CLK_1") (class "Default")
      (node (ref "R7") (pin "1") (pinfunction "1_1") (pintype "passive"))
      (node (ref "U3") (pin "52") (pinfunction "PMWR/RP68/RD4_52") (pintype "passive"))
      (node (ref "U3") (pin "53") (pinfunction "PMRD/RP69/RD5_53") (pintype "passive"))
      (node (ref "U3") (pin "54") (pinfunction "C3IN2-/RP70/RD6_54") (pintype "passive"))
      (node (ref "U3") (pin "55") (pinfunction "C3IN1+/VCMPST3/RP71/RD7_55") (pintype "passive"))
    )
    (net (code "16") (name "/MCU_REF_CLK_2") (class "Default")
      (node (ref "R18") (pin "1") (pinfunction "1_1") (pintype "passive"))
      (node (ref "U3") (pin "46") (pinfunction "INT0/DMH/RP64/RD0_46") (pintype "passive"))
      (node (ref "U3") (pin "49") (pinfunction "VCPCON/RP65/RD1_49") (pintype "passive"))
      (node (ref "U3") (pin "50") (pinfunction "DPH/RP66/RD2_50") (pintype "passive"))
      (node (ref "U3") (pin "51") (pinfunction "PMBE/RP67/RD3_51") (pintype "passive"))
    )
    (net (code "17") (name "/MEAS12") (class "Default")
      (node (ref "C1") (pin "1") (pinfunction "1_1") (pintype "passive"))
      (node (ref "R4") (pin "2") (pinfunction "2_2") (pintype "passive"))
      (node (ref "R5") (pin "2") (pinfunction "2_2") (pintype "passive"))
      (node (ref "U3") (pin "18") (pinfunction "PGED1/AN7/RCV/RPI39/RB7_18") (pintype "passive"))
    )
    (net (code "18") (name "/Main OSC In") (class "Default")
      (node (ref "C10") (pin "1") (pinfunction "1_1") (pintype "passive"))
      (node (ref "U3") (pin "39") (pinfunction "OSC1/RPI60/RC12_39") (pintype "passive"))
      (node (ref "Y1") (pin "1") (pinfunction "1_1") (pintype "passive"))
    )
    (net (code "19") (name "/Main OSC Out") (class "Default")
      (node (ref "C11") (pin "1") (pinfunction "1_1") (pintype "passive"))
      (node (ref "U3") (pin "40") (pinfunction "OSC2/CLKO/RC15_40") (pintype "passive"))
      (node (ref "Y1") (pin "2") (pinfunction "2_2") (pintype "passive"))
    )
    (net (code "20") (name "/ORANGE") (class "Default")
      (node (ref "D4") (pin "2") (pinfunction "A_2") (pintype "passive"))
      (node (ref "U3") (pin "45") (pinfunction "PMCS1/RPI75/RD11_45") (pintype "passive"))
    )
    (net (code "21") (name "/PGC") (class "Default")
      (node (ref "J1") (pin "5") (pinfunction "5_5") (pintype "passive"))
      (node (ref "U3") (pin "15") (pinfunction "PGEC3/AN1/VREF-/RPI33/RB1_15") (pintype "passive"))
    )
    (net (code "22") (name "/PGD") (class "Default")
      (node (ref "J1") (pin "4") (pinfunction "4_4") (pintype "passive"))
      (node (ref "U3") (pin "16") (pinfunction "PGED3/AN0/VREF+/RPI32/RB0_16") (pintype "passive"))
    )
    (net (code "23") (name "/PLL_REF_CLK_1") (class "Default")
      (node (ref "R7") (pin "2") (pinfunction "2_2") (pintype "passive"))
      (node (ref "R8") (pin "2") (pinfunction "2_2") (pintype "passive"))
    )
    (net (code "24") (name "/PLL_REF_CLK_2") (class "Default")
      (node (ref "R18") (pin "2") (pinfunction "2_2") (pintype "passive"))
      (node (ref "R8") (pin "1") (pinfunction "1_1") (pintype "passive"))
    )
    (net (code "25") (name "/PWM1H") (class "Default")
      (node (ref "U3") (pin "61") (pinfunction "AN25/PWM1H/PMD1/RPI81/RE1_61") (pintype "passive"))
    )
    (net (code "26") (name "/PWM1L") (class "Default")
      (node (ref "U3") (pin "60") (pinfunction "AN24/PWM1L/PMD0/RP80/RE0_60") (pintype "passive"))
    )
    (net (code "27") (name "/PWM2H") (class "Default")
      (node (ref "U3") (pin "63") (pinfunction "AN27/PWM2H/PMD3/RPI83/RE3_63") (pintype "passive"))
    )
    (net (code "28") (name "/PWM2L") (class "Default")
      (node (ref "U3") (pin "62") (pinfunction "AN26/PWM2L/PMD2/RP82/RE2_62") (pintype "passive"))
    )
    (net (code "29") (name "/PWM3H") (class "Default")
      (node (ref "U3") (pin "1") (pinfunction "AN29/PWM3H/PMD5/RP85/RE5_1") (pintype "passive"))
    )
    (net (code "30") (name "/PWM3L") (class "Default")
      (node (ref "U3") (pin "64") (pinfunction "AN28/PWM3L/PMD4/RP84/RE4_64") (pintype "passive"))
    )
    (net (code "31") (name "/PWM4H") (class "Default")
      (node (ref "U3") (pin "3") (pinfunction "AN31/PWM4H/PMD7/RP87/RE7_3") (pintype "passive"))
    )
    (net (code "32") (name "/PWM4L") (class "Default")
      (node (ref "U3") (pin "2") (pinfunction "AN30/PWM4L/PMD6/RPI86/RE6_2") (pintype "passive"))
    )
    (net (code "33") (name "/RED") (class "Default")
      (node (ref "D1") (pin "2") (pinfunction "A_2") (pintype "passive"))
      (node (ref "U3") (pin "48") (pinfunction "PGEC2/SOSCO/C3IN1-/T1CK/RPI62/RC14_48") (pintype "passive"))
    )
    (net (code "34") (name "/RESET_COLD_L") (class "Default")
      (node (ref "D29") (pin "2") (pinfunction "A_2") (pintype "passive"))
      (node (ref "R21") (pin "2") (pinfunction "2_2") (pintype "passive"))
    )
    (net (code "35") (name "/TXD_0") (class "Default")
      (node (ref "R72") (pin "2") (pinfunction "2_2") (pintype "passive"))
      (node (ref "U3") (pin "6") (pinfunction "C2IN3-/SDO2/PMA3/RP120/RG8_6") (pintype "passive"))
    )
    (net (code "36") (name "/TXD_1") (class "Default")
      (node (ref "R72") (pin "1") (pinfunction "1_1") (pintype "passive"))
      (node (ref "R73") (pin "1") (pinfunction "1_1") (pintype "passive"))
    )
    (net (code "37") (name "/TXD_9") (class "Default")
      (node (ref "Q51") (pin "1") (pinfunction "G_1") (pintype "passive"))
    )
    (net (code "38") (name "/TXD_10") (class "Default")
      (node (ref "Q51") (pin "3") (pinfunction "D_3") (pintype "passive"))
      (node (ref "R74") (pin "2") (pinfunction "2_2") (pintype "passive"))
      (node (ref "U3") (pin "5") (pinfunction "C1IN1-/SDI2/PMA4/RPI119/RG7_5") (pintype "passive"))
    )
    (net (code "39") (name "/USB5.0V") (class "Default")
      (node (ref "D6") (pin "4") (pinfunction "4_4") (pintype "passive"))
      (node (ref "D6") (pin "6") (pinfunction "6_6") (pintype "passive"))
      (node (ref "J2") (pin "1") (pinfunction "1_1") (pintype "passive"))
      (node (ref "R10") (pin "1") (pinfunction "1_1") (pintype "passive"))
      (node (ref "R11") (pin "2") (pinfunction "2_2") (pintype "passive"))
    )
    (net (code "40") (name "/VCAP") (class "Default")
      (node (ref "C2") (pin "1") (pinfunction "1_1") (pintype "passive"))
      (node (ref "U3") (pin "56") (pinfunction "VCAP_56") (pintype "passive"))
    )
    (net (code "41") (name "/YELLOW") (class "Default")
      (node (ref "D3") (pin "2") (pinfunction "A_2") (pintype "passive"))
      (node (ref "U3") (pin "44") (pinfunction "ASCL1/PMCS2/RPI74/RD10_44") (pintype "passive"))
    )
    (net (code "42") (name "GND") (class "Default")
      (node (ref "C1") (pin "2") (pinfunction "2_2") (pintype "passive"))
      (node (ref "C10") (pin "2") (pinfunction "2_2") (pintype "passive"))
      (node (ref "C11") (pin "2") (pinfunction "2_2") (pintype "passive"))
      (node (ref "C12") (pin "2") (pinfunction "2_2") (pintype "passive"))
      (node (ref "C13") (pin "1") (pinfunction "1_1") (pintype "passive"))
      (node (ref "C14") (pin "2") (pinfunction "2_2") (pintype "passive"))
      (node (ref "C15") (pin "2") (pinfunction "2_2") (pintype "passive"))
      (node (ref "C16") (pin "2") (pinfunction "2_2") (pintype "passive"))
      (node (ref "C17") (pin "2") (pinfunction "2_2") (pintype "passive"))
      (node (ref "C2") (pin "2") (pinfunction "2_2") (pintype "passive"))
      (node (ref "C3") (pin "2") (pinfunction "2_2") (pintype "passive"))
      (node (ref "C347") (pin "2") (pinfunction "2_2") (pintype "passive"))
      (node (ref "C4") (pin "2") (pinfunction "2_2") (pintype "passive"))
      (node (ref "C5") (pin "2") (pinfunction "2_2") (pintype "passive"))
      (node (ref "C6") (pin "2") (pinfunction "2_2") (pintype "passive"))
      (node (ref "C7") (pin "2") (pinfunction "2_2") (pintype "passive"))
      (node (ref "C8") (pin "2") (pinfunction "2_2") (pintype "passive"))
      (node (ref "C9") (pin "2") (pinfunction "2_2") (pintype "passive"))
      (node (ref "D1") (pin "1") (pinfunction "C_1") (pintype "passive"))
      (node (ref "D2") (pin "1") (pinfunction "C_1") (pintype "passive"))
      (node (ref "D26") (pin "2") (pinfunction "A_2") (pintype "passive"))
      (node (ref "D27") (pin "2") (pinfunction "A_2") (pintype "passive"))
      (node (ref "D28") (pin "2") (pinfunction "A_2") (pintype "passive"))
      (node (ref "D3") (pin "1") (pinfunction "C_1") (pintype "passive"))
      (node (ref "D4") (pin "1") (pinfunction "C_1") (pintype "passive"))
      (node (ref "D6") (pin "2") (pinfunction "2_2") (pintype "passive"))
      (node (ref "D6") (pin "5") (pinfunction "5_5") (pintype "passive"))
      (node (ref "D9") (pin "2") (pinfunction "A_2") (pintype "passive"))
      (node (ref "J1") (pin "3") (pinfunction "3_3") (pintype "passive"))
      (node (ref "J10") (pin "4") (pinfunction "4_4") (pintype "passive"))
      (node (ref "J10") (pin "5") (pinfunction "5_5") (pintype "passive"))
      (node (ref "J10") (pin "6") (pinfunction "6_6") (pintype "passive"))
      (node (ref "J11") (pin "4") (pinfunction "4_4") (pintype "passive"))
      (node (ref "J11") (pin "5") (pinfunction "5_5") (pintype "passive"))
      (node (ref "J11") (pin "6") (pinfunction "6_6") (pintype "passive"))
      (node (ref "J12") (pin "4") (pinfunction "4_4") (pintype "passive"))
      (node (ref "J12") (pin "5") (pinfunction "5_5") (pintype "passive"))
      (node (ref "J12") (pin "6") (pinfunction "6_6") (pintype "passive"))
      (node (ref "J2") (pin "5") (pinfunction "5_5") (pintype "passive"))
      (node (ref "J2") (pin "6") (pinfunction "6_6") (pintype "passive"))
      (node (ref "J2") (pin "7") (pinfunction "7_7") (pintype "passive"))
      (node (ref "J2") (pin "8") (pinfunction "8_8") (pintype "passive"))
      (node (ref "J2") (pin "9") (pinfunction "9_9") (pintype "passive"))
      (node (ref "J3") (pin "2") (pinfunction "2_2") (pintype "passive"))
      (node (ref "J4") (pin "4") (pinfunction "4_4") (pintype "passive"))
      (node (ref "J4") (pin "5") (pinfunction "5_5") (pintype "passive"))
      (node (ref "J4") (pin "6") (pinfunction "6_6") (pintype "passive"))
      (node (ref "J5") (pin "4") (pinfunction "4_4") (pintype "passive"))
      (node (ref "J5") (pin "5") (pinfunction "5_5") (pintype "passive"))
      (node (ref "J5") (pin "6") (pinfunction "6_6") (pintype "passive"))
      (node (ref "J6") (pin "4") (pinfunction "4_4") (pintype "passive"))
      (node (ref "J6") (pin "5") (pinfunction "5_5") (pintype "passive"))
      (node (ref "J6") (pin "6") (pinfunction "6_6") (pintype "passive"))
      (node (ref "J7") (pin "4") (pinfunction "4_4") (pintype "passive"))
      (node (ref "J7") (pin "5") (pinfunction "5_5") (pintype "passive"))
      (node (ref "J7") (pin "6") (pinfunction "6_6") (pintype "passive"))
      (node (ref "J8") (pin "4") (pinfunction "4_4") (pintype "passive"))
      (node (ref "J8") (pin "5") (pinfunction "5_5") (pintype "passive"))
      (node (ref "J8") (pin "6") (pinfunction "6_6") (pintype "passive"))
      (node (ref "Q51") (pin "2") (pinfunction "S_2") (pintype "passive"))
      (node (ref "R17") (pin "2") (pinfunction "2_2") (pintype "passive"))
      (node (ref "R5") (pin "1") (pinfunction "1_1") (pintype "passive"))
      (node (ref "R73") (pin "2") (pinfunction "2_2") (pintype "passive"))
      (node (ref "U3") (pin "20") (pinfunction "AVSS_20") (pintype "passive"))
      (node (ref "U3") (pin "25") (pinfunction "VSS_25") (pintype "passive"))
      (node (ref "U3") (pin "41") (pinfunction "VSS_41") (pintype "passive"))
      (node (ref "U3") (pin "9") (pinfunction "VSS_9") (pintype "passive"))
      (node (ref "U4") (pin "2") (pinfunction "GND_2") (pintype "passive"))
      (node (ref "U4") (pin "3") (pinfunction "GND_3") (pintype "passive"))
      (node (ref "U4") (pin "4") (pinfunction "N.C._4") (pintype "passive"))
      (node (ref "U4") (pin "5") (pinfunction "N.C._5") (pintype "passive"))
      (node (ref "U4") (pin "6") (pinfunction "GND_6") (pintype "passive"))
      (node (ref "U4") (pin "7") (pinfunction "GND_7") (pintype "passive"))
      (node (ref "U5") (pin "2") (pinfunction "GND_2") (pintype "passive"))
      (node (ref "U6") (pin "6") (pinfunction "GND_6") (pintype "passive"))
      (node (ref "U6") (pin "7") (pinfunction "GND_7") (pintype "passive"))
      (node (ref "U7") (pin "4") (pinfunction "GND_4") (pintype "passive"))
      (node (ref "U8") (pin "4") (pinfunction "GND_4") (pintype "passive"))
      (node (ref "U9") (pin "6") (pinfunction "GND_6") (pintype "passive"))
      (node (ref "U9") (pin "7") (pinfunction "GND_7") (pintype "passive"))
    )
    (net (code "43") (name "Net-(D29-C)") (class "Default")
      (node (ref "D29") (pin "1") (pinfunction "C_1") (pintype "passive"))
      (node (ref "U3") (pin "8") (pinfunction "C2IN1-/PMA2/RPI121/RG9_8") (pintype "passive"))
    )
    (net (code "44") (name "Net-(U3-AN2{slash}C2IN2-{slash}VMIO{slash}RPI34{slash}RB2)") (class "Default")
      (node (ref "TP7") (pin "1") (pinfunction "1_1") (pintype "passive"))
      (node (ref "U3") (pin "14") (pinfunction "AN2/C2IN2-/VMIO/RPI34/RB2_14") (pintype "passive"))
    )
    (net (code "45") (name "Net-(U3-AN3{slash}C2IN1+{slash}VPIO{slash}RPI35{slash}RB3)") (class "Default")
      (node (ref "TP6") (pin "1") (pinfunction "1_1") (pintype "passive"))
      (node (ref "U3") (pin "13") (pinfunction "AN3/C2IN1+/VPIO/RPI35/RB3_13") (pintype "passive"))
    )
    (net (code "46") (name "Net-(U3-AN4{slash}C1IN2-{slash}USBOEN{slash}RPI36{slash}RB4)") (class "Default")
      (node (ref "TP5") (pin "1") (pinfunction "1_1") (pintype "passive"))
      (node (ref "U3") (pin "12") (pinfunction "AN4/C1IN2-/USBOEN/RPI36/RB4_12") (pintype "passive"))
    )
    (net (code "47") (name "Net-(U3-AN5{slash}C1IN1+{slash}VBUSON{slash}VBUSST{slash}RPI37{slash}RB5)") (class "Default")
      (node (ref "TP3") (pin "1") (pinfunction "1_1") (pintype "passive"))
      (node (ref "U3") (pin "11") (pinfunction "AN5/C1IN1+/VBUSON/VBUSST/RPI37/RB5_11") (pintype "passive"))
    )
    (net (code "48") (name "Net-(U3-AN8{slash}PMA6{slash}RPI40{slash}RB8)") (class "Default")
      (node (ref "TP10") (pin "1") (pinfunction "1_1") (pintype "passive"))
      (node (ref "U3") (pin "21") (pinfunction "AN8/PMA6/RPI40/RB8_21") (pintype "passive"))
    )
    (net (code "49") (name "Net-(U3-AN9{slash}PMA7{slash}{slash}RPI41{slash}RB9)") (class "Default")
      (node (ref "TP11") (pin "1") (pinfunction "1_1") (pintype "passive"))
      (node (ref "U3") (pin "22") (pinfunction "AN9/PMA7//RPI41/RB9_22") (pintype "passive"))
    )
    (net (code "50") (name "Net-(U3-AN14{slash}PMA1{slash}RPI46{slash}RB14)") (class "Default")
      (node (ref "TP124") (pin "1") (pinfunction "1_1") (pintype "passive"))
      (node (ref "U3") (pin "29") (pinfunction "AN14/PMA1/RPI46/RB14_29") (pintype "passive"))
    )
    (net (code "51") (name "Net-(U3-AN15{slash}PMA0{slash}RPI47{slash}RB15)") (class "Default")
      (node (ref "TP125") (pin "1") (pinfunction "1_1") (pintype "passive"))
      (node (ref "U3") (pin "30") (pinfunction "AN15/PMA0/RPI47/RB15_30") (pintype "passive"))
    )
    (net (code "52") (name "Net-(U3-ASDA1{slash}DPLN{slash}RPI73{slash}RD9)") (class "Default")
      (node (ref "TP12") (pin "1") (pinfunction "1_1") (pintype "passive"))
      (node (ref "U3") (pin "43") (pinfunction "ASDA1/DPLN/RPI73/RD9_43") (pintype "passive"))
    )
    (net (code "53") (name "Net-(U3-C1IN3-{slash}SCK2{slash}PMA5{slash}RP118{slash}RG6)") (class "Default")
      (node (ref "TP130") (pin "1") (pinfunction "1_1") (pintype "passive"))
      (node (ref "U3") (pin "4") (pinfunction "C1IN3-/SCK2/PMA5/RP118/RG6_4") (pintype "passive"))
    )
    (net (code "54") (name "Net-(U3-RTCC{slash}DMLN{slash}RPI72{slash}RD8)") (class "Default")
      (node (ref "TP13") (pin "1") (pinfunction "1_1") (pintype "passive"))
      (node (ref "U3") (pin "42") (pinfunction "RTCC/DMLN/RPI72/RD8_42") (pintype "passive"))
    )
    (net (code "55") (name "Net-(U3-SCL2{slash}PMA8{slash}RP101{slash}RF5)") (class "Default")
      (node (ref "TP127") (pin "1") (pinfunction "1_1") (pintype "passive"))
      (node (ref "U3") (pin "32") (pinfunction "SCL2/PMA8/RP101/RF5_32") (pintype "passive"))
    )
    (net (code "56") (name "Net-(U3-SDA2{slash}PMA9{slash}RP100{slash}RF4)") (class "Default")
      (node (ref "TP126") (pin "1") (pinfunction "1_1") (pintype "passive"))
      (node (ref "U3") (pin "31") (pinfunction "SDA2/PMA9/RP100/RF4_31") (pintype "passive"))
    )
    (net (code "57") (name "Net-(U3-TCK{slash}AN12{slash}PMA11{slash}RPI44{slash}RB12)") (class "Default")
      (node (ref "TP2") (pin "1") (pinfunction "1_1") (pintype "passive"))
      (node (ref "U3") (pin "27") (pinfunction "TCK/AN12/PMA11/RPI44/RB12_27") (pintype "passive"))
    )
    (net (code "58") (name "Net-(U3-TDI{slash}AN13{slash}PMA10{slash}RPI45{slash}RB13)") (class "Default")
      (node (ref "TP123") (pin "1") (pinfunction "1_1") (pintype "passive"))
      (node (ref "U3") (pin "28") (pinfunction "TDI/AN13/PMA10/RPI45/RB13_28") (pintype "passive"))
    )
    (net (code "59") (name "Net-(U3-TDO{slash}AN11{slash}PMA12{slash}RPI43{slash}RB11)") (class "Default")
      (node (ref "TP132") (pin "1") (pinfunction "1_1") (pintype "passive"))
      (node (ref "U3") (pin "24") (pinfunction "TDO/AN11/PMA12/RPI43/RB11_24") (pintype "passive"))
    )
    (net (code "60") (name "Net-(U3-TMS{slash}AN10{slash}CVREF{slash}PMA13{slash}RPI42{slash}RB10)") (class "Default")
      (node (ref "TP131") (pin "1") (pinfunction "1_1") (pintype "passive"))
      (node (ref "U3") (pin "23") (pinfunction "TMS/AN10/CVREF/PMA13/RPI42/RB10_23") (pintype "passive"))
    )
    (net (code "61") (name "Net-(U3-USBID{slash}RP99{slash}RF3)") (class "Default")
      (node (ref "TP21") (pin "1") (pinfunction "1_1") (pintype "passive"))
      (node (ref "U3") (pin "33") (pinfunction "USBID/RP99/RF3_33") (pintype "passive"))
    )
    (net (code "62") (name "Net-(U3-VCMPST1{slash}RP96{slash}RF0)") (class "Default")
      (node (ref "TP129") (pin "1") (pinfunction "1_1") (pintype "passive"))
      (node (ref "U3") (pin "58") (pinfunction "VCMPST1/RP96/RF0_58") (pintype "passive"))
    )
    (net (code "63") (name "Net-(U3-VCMPST2{slash}RP97{slash}RF1)") (class "Default")
      (node (ref "TP128") (pin "1") (pinfunction "1_1") (pintype "passive"))
      (node (ref "U3") (pin "59") (pinfunction "VCMPST2/RP97/RF1_59") (pintype "passive"))
    )
    (net (code "64") (name "Net-(U9-ADJ)") (class "Default")
      (node (ref "R16") (pin "2") (pinfunction "2_2") (pintype "passive"))
      (node (ref "R17") (pin "1") (pinfunction "1_1") (pintype "passive"))
      (node (ref "U9") (pin "2") (pinfunction "ADJ_2") (pintype "passive"))
    )
    (net (code "65") (name "unconnected-(J2-Pad4)") (class "Default")
      (node (ref "J2") (pin "4") (pinfunction "4_4") (pintype "passive+no_connect"))
    )
    (net (code "66") (name "unconnected-(U5-N.C.-Pad4)") (class "Default")
      (node (ref "U5") (pin "4") (pinfunction "N.C._4") (pintype "passive+no_connect"))
    )
    (net (code "67") (name "unconnected-(U6-NC-Pad2)") (class "Default")
      (node (ref "U6") (pin "2") (pinfunction "NC_2") (pintype "passive+no_connect"))
    )
    (net (code "68") (name "unconnected-(U6-NC-Pad3)") (class "Default")
      (node (ref "U6") (pin "3") (pinfunction "NC_3") (pintype "passive+no_connect"))
    )
    (net (code "69") (name "unconnected-(U6-NC-Pad4)") (class "Default")
      (node (ref "U6") (pin "4") (pinfunction "NC_4") (pintype "passive+no_connect"))
    )
    (net (code "70") (name "unconnected-(U9-NC-Pad3)") (class "Default")
      (node (ref "U9") (pin "3") (pinfunction "NC_3") (pintype "passive+no_connect"))
    )
    (net (code "71") (name "unconnected-(U9-NC-Pad4)") (class "Default")
      (node (ref "U9") (pin "4") (pinfunction "NC_4") (pintype "passive+no_connect"))
    )
  )
)
